# RevellerZero.net
KiCad netlist of a schematic drawn in EAGLE
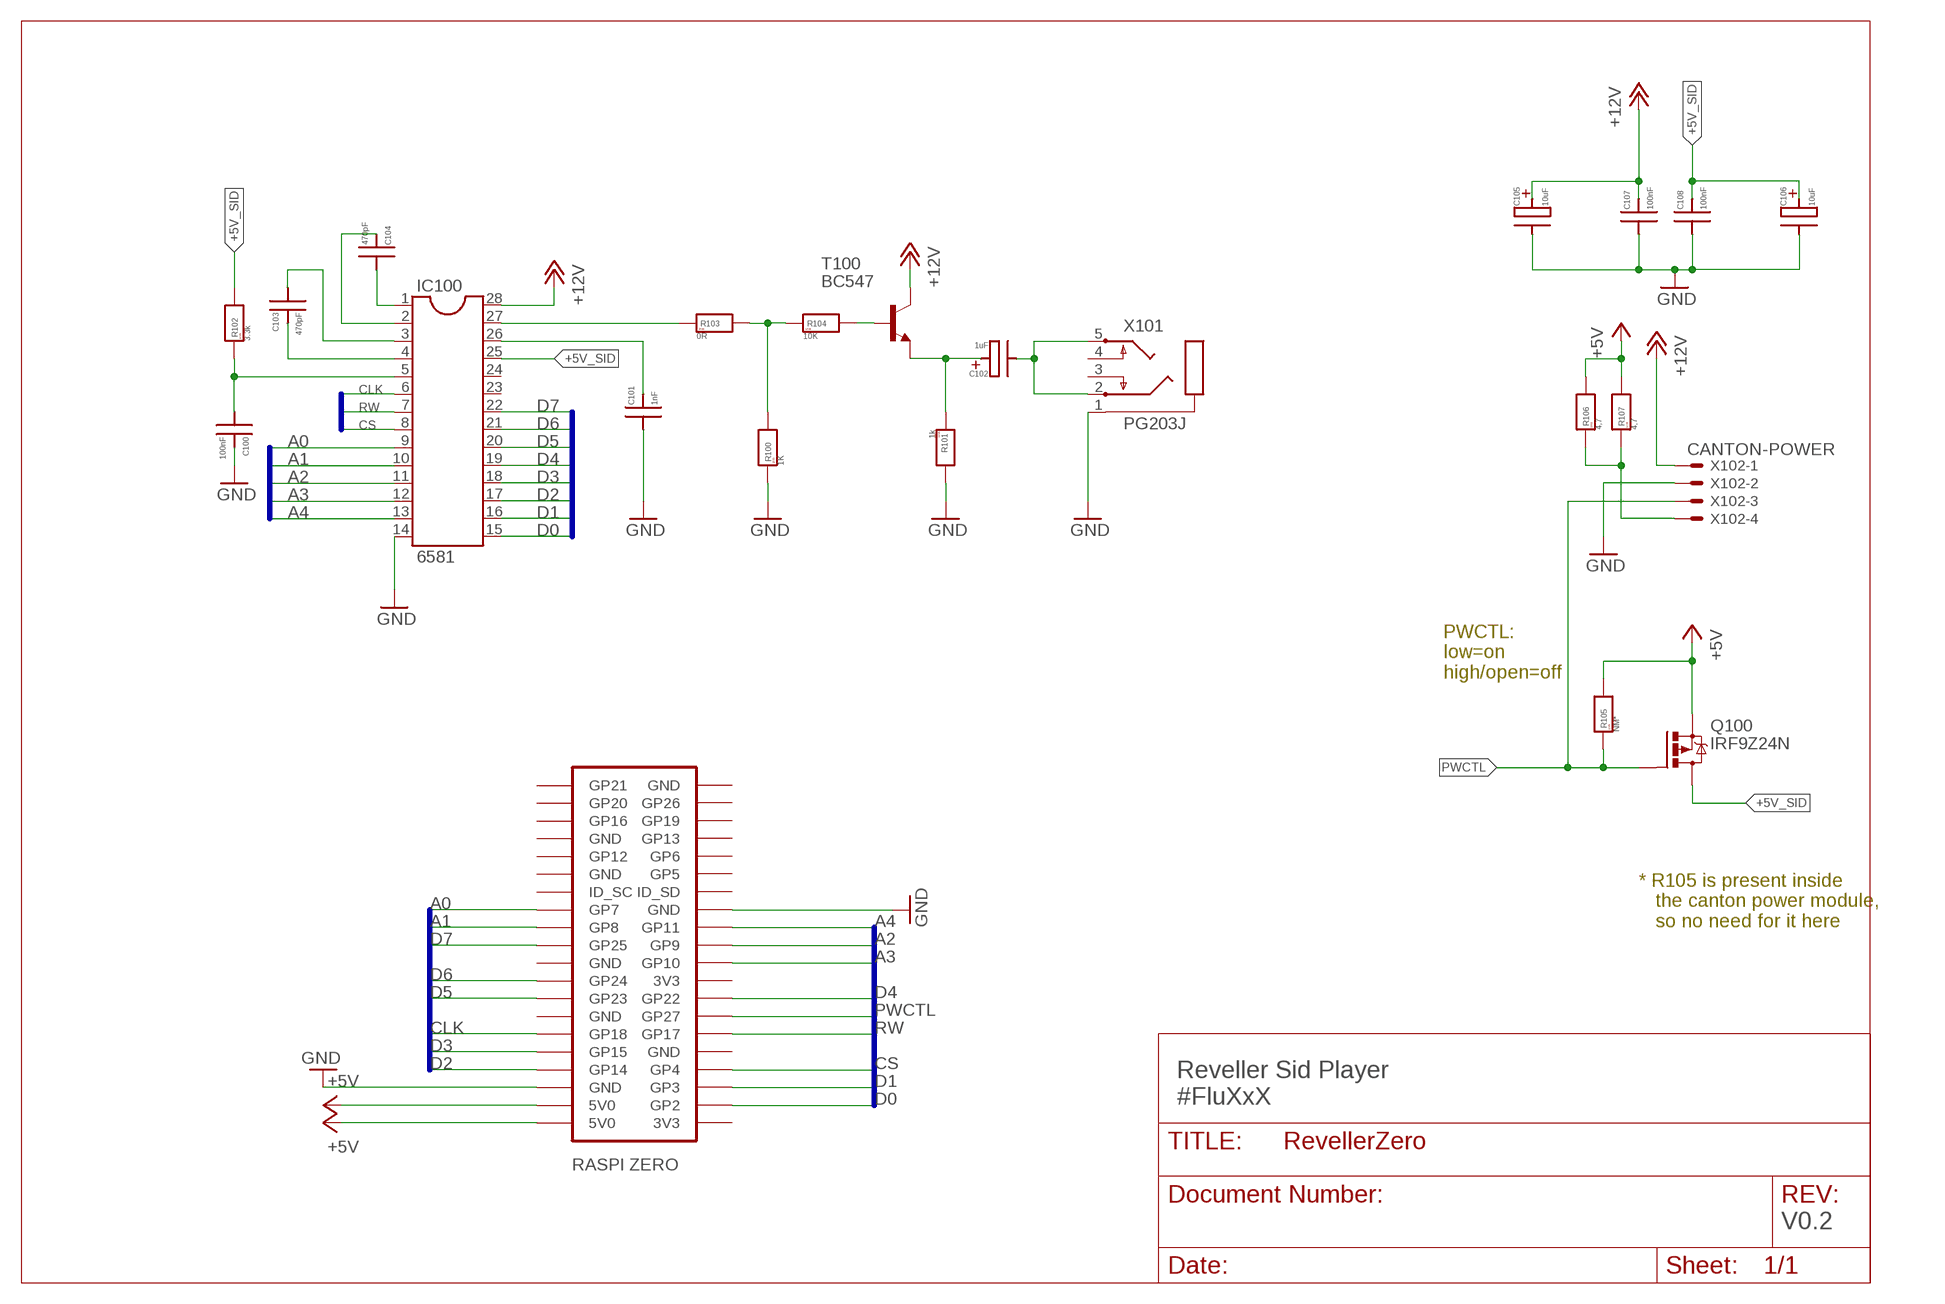
[diagram p0: schematic, sheet 1]

(export (version "E")
  (design (tool "Eeschema 10.0.6"))
  (components
    (comp (ref "C100")
      (value "100nF")
      (footprint "eagle-import:SMD-IPC_C1206")
      (libsource (lib "eagle-import") (part "SMD-IPC_CAPC1206"))
    )
    (comp (ref "C101")
      (value "1nF")
      (footprint "eagle-import:SMD-IPC_C1206")
      (libsource (lib "eagle-import") (part "SMD-IPC_CAPC1206"))
    )
    (comp (ref "C102")
      (value "1uF")
      (footprint "eagle-import:PXE-H")
      (libsource (lib "eagle-import") (part "SMD-IPC_CAPPOLPXE_H"))
    )
    (comp (ref "C103")
      (value "470pF")
      (footprint "eagle-import:SMD-IPC_C1206")
      (libsource (lib "eagle-import") (part "SMD-IPC_CAPC1206"))
    )
    (comp (ref "C104")
      (value "470pF")
      (footprint "eagle-import:SMD-IPC_C1206")
      (libsource (lib "eagle-import") (part "SMD-IPC_CAPC1206"))
    )
    (comp (ref "C105")
      (value "10uF")
      (footprint "eagle-import:SMD-IPC_CT7343")
      (libsource (lib "eagle-import") (part "SMD-IPC_CAPPOLC7343"))
    )
    (comp (ref "C106")
      (value "10uF")
      (footprint "eagle-import:SMD-IPC_CT7343")
      (libsource (lib "eagle-import") (part "SMD-IPC_CAPPOLC7343"))
    )
    (comp (ref "C107")
      (value "100nF")
      (footprint "eagle-import:SMD-IPC_C1206")
      (libsource (lib "eagle-import") (part "SMD-IPC_CAPC1206"))
    )
    (comp (ref "C108")
      (value "100nF")
      (footprint "eagle-import:SMD-IPC_C1206")
      (libsource (lib "eagle-import") (part "SMD-IPC_CAPC1206"))
    )
    (comp (ref "IC100")
      (value "6581")
      (footprint "eagle-import:DIL28-6")
      (libsource (lib "eagle-import") (part "DIL28"))
    )
    (comp (ref "Q100")
      (value "IRF9Z24N")
      (footprint "eagle-import:TO220BV")
      (libsource (lib "eagle-import") (part "IRF9530"))
    )
    (comp (ref "R100")
      (value "1K")
      (footprint "eagle-import:SMD-IPC_R1206")
      (libsource (lib "eagle-import") (part "SMD-IPC_RESR1206"))
    )
    (comp (ref "R101")
      (value "1k")
      (footprint "eagle-import:SMD-IPC_R1206")
      (libsource (lib "eagle-import") (part "SMD-IPC_RESR1206"))
    )
    (comp (ref "R102")
      (value "3.3k")
      (footprint "eagle-import:SMD-IPC_R1206")
      (libsource (lib "eagle-import") (part "SMD-IPC_RESR1206"))
    )
    (comp (ref "R103")
      (value "0R")
      (footprint "eagle-import:SMD-IPC_R1206")
      (libsource (lib "eagle-import") (part "SMD-IPC_RESR1206"))
    )
    (comp (ref "R104")
      (value "10K")
      (footprint "eagle-import:SMD-IPC_R1206")
      (libsource (lib "eagle-import") (part "SMD-IPC_RESR1206"))
    )
    (comp (ref "R105")
      (value "NM*")
      (footprint "eagle-import:SMD-IPC_R1206")
      (libsource (lib "eagle-import") (part "SMD-IPC_RESR1206"))
    )
    (comp (ref "R106")
      (value "4,7")
      (footprint "eagle-import:SMD-IPC_R1206")
      (libsource (lib "eagle-import") (part "SMD-IPC_RESR1206"))
    )
    (comp (ref "R107")
      (value "4,7")
      (footprint "eagle-import:SMD-IPC_R1206")
      (libsource (lib "eagle-import") (part "SMD-IPC_RESR1206"))
    )
    (comp (ref "T100")
      (value "BC547")
      (footprint "eagle-import:TO92")
      (libsource (lib "eagle-import") (part "BC547"))
    )
    (comp (ref "U$1")
      (value "ZERO")
      (footprint "eagle-import:ZERO")
      (libsource (lib "eagle-import") (part "ZERO"))
    )
    (comp (ref "X101")
      (value "PG203J")
      (footprint "eagle-import:PG203J")
      (libsource (lib "eagle-import") (part "PG203J"))
    )
    (comp (ref "X102")
      (value "CANTON-POWER")
      (footprint "eagle-import:22-23-2041")
      (fields (field (name "MF") "MOLEX") (field (name "MPN") "22-23-2041"))
      (libsource (lib "eagle-import") (part "22-23-2041"))
    )
  )
  (nets
    (net (code "1") (name "+5V") (class "Default")
      (node (ref "Q100") (pin "S") (pinfunction "S_S") (pintype "passive"))
      (node (ref "R105") (pin "2") (pinfunction "2_2") (pintype "passive"))
      (node (ref "R106") (pin "2") (pinfunction "2_2") (pintype "passive"))
      (node (ref "R107") (pin "2") (pinfunction "2_2") (pintype "passive"))
      (node (ref "U$1") (pin "2") (pinfunction "5V0_2") (pintype "bidirectional"))
      (node (ref "U$1") (pin "4") (pinfunction "5V0_4") (pintype "bidirectional"))
    )
    (net (code "2") (name "+5V_SID") (class "Default")
      (node (ref "C106") (pin "+") (pinfunction "+_+") (pintype "passive"))
      (node (ref "C108") (pin "+") (pinfunction "2_+") (pintype "passive"))
      (node (ref "IC100") (pin "25") (pinfunction "25_25") (pintype "passive"))
      (node (ref "Q100") (pin "D") (pinfunction "D_D") (pintype "passive"))
      (node (ref "R102") (pin "2") (pinfunction "2_2") (pintype "passive"))
    )
    (net (code "3") (name "+12V") (class "Default")
      (node (ref "C105") (pin "+") (pinfunction "+_+") (pintype "passive"))
      (node (ref "C107") (pin "+") (pinfunction "2_+") (pintype "passive"))
      (node (ref "IC100") (pin "28") (pinfunction "28_28") (pintype "passive"))
      (node (ref "T100") (pin "3") (pinfunction "C_3") (pintype "passive"))
      (node (ref "X102") (pin "1") (pinfunction "S_1") (pintype "passive"))
    )
    (net (code "4") (name "/A0") (class "Default")
      (node (ref "IC100") (pin "9") (pinfunction "9_9") (pintype "passive"))
      (node (ref "U$1") (pin "26") (pinfunction "GP7_26") (pintype "bidirectional"))
    )
    (net (code "5") (name "/A1") (class "Default")
      (node (ref "IC100") (pin "10") (pinfunction "10_10") (pintype "passive"))
      (node (ref "U$1") (pin "24") (pinfunction "GP8_24") (pintype "bidirectional"))
    )
    (net (code "6") (name "/A2") (class "Default")
      (node (ref "IC100") (pin "11") (pinfunction "11_11") (pintype "passive"))
      (node (ref "U$1") (pin "21") (pinfunction "GP9_21") (pintype "bidirectional"))
    )
    (net (code "7") (name "/A3") (class "Default")
      (node (ref "IC100") (pin "12") (pinfunction "12_12") (pintype "passive"))
      (node (ref "U$1") (pin "19") (pinfunction "GP10_19") (pintype "bidirectional"))
    )
    (net (code "8") (name "/A4") (class "Default")
      (node (ref "IC100") (pin "13") (pinfunction "13_13") (pintype "passive"))
      (node (ref "U$1") (pin "23") (pinfunction "GP11_23") (pintype "bidirectional"))
    )
    (net (code "9") (name "/CLK") (class "Default")
      (node (ref "IC100") (pin "6") (pinfunction "6_6") (pintype "passive"))
      (node (ref "U$1") (pin "12") (pinfunction "GP18_12") (pintype "bidirectional"))
    )
    (net (code "10") (name "/CS") (class "Default")
      (node (ref "IC100") (pin "8") (pinfunction "8_8") (pintype "passive"))
      (node (ref "U$1") (pin "7") (pinfunction "GP4_7") (pintype "bidirectional"))
    )
    (net (code "11") (name "/D0") (class "Default")
      (node (ref "IC100") (pin "15") (pinfunction "15_15") (pintype "passive"))
      (node (ref "U$1") (pin "3") (pinfunction "GP2_3") (pintype "bidirectional"))
    )
    (net (code "12") (name "/D1") (class "Default")
      (node (ref "IC100") (pin "16") (pinfunction "16_16") (pintype "passive"))
      (node (ref "U$1") (pin "5") (pinfunction "GP3_5") (pintype "bidirectional"))
    )
    (net (code "13") (name "/D2") (class "Default")
      (node (ref "IC100") (pin "17") (pinfunction "17_17") (pintype "passive"))
      (node (ref "U$1") (pin "8") (pinfunction "GP14_8") (pintype "bidirectional"))
    )
    (net (code "14") (name "/D3") (class "Default")
      (node (ref "IC100") (pin "18") (pinfunction "18_18") (pintype "passive"))
      (node (ref "U$1") (pin "10") (pinfunction "GP15_10") (pintype "bidirectional"))
    )
    (net (code "15") (name "/D4") (class "Default")
      (node (ref "IC100") (pin "19") (pinfunction "19_19") (pintype "passive"))
      (node (ref "U$1") (pin "15") (pinfunction "GP22_15") (pintype "bidirectional"))
    )
    (net (code "16") (name "/D5") (class "Default")
      (node (ref "IC100") (pin "20") (pinfunction "20_20") (pintype "passive"))
      (node (ref "U$1") (pin "16") (pinfunction "GP23_16") (pintype "bidirectional"))
    )
    (net (code "17") (name "/D6") (class "Default")
      (node (ref "IC100") (pin "21") (pinfunction "21_21") (pintype "passive"))
      (node (ref "U$1") (pin "18") (pinfunction "GP24_18") (pintype "bidirectional"))
    )
    (net (code "18") (name "/D7") (class "Default")
      (node (ref "IC100") (pin "22") (pinfunction "22_22") (pintype "passive"))
      (node (ref "U$1") (pin "22") (pinfunction "GP25_22") (pintype "bidirectional"))
    )
    (net (code "19") (name "/RW") (class "Default")
      (node (ref "IC100") (pin "7") (pinfunction "7_7") (pintype "passive"))
      (node (ref "U$1") (pin "11") (pinfunction "GP17_11") (pintype "bidirectional"))
    )
    (net (code "20") (name "GND") (class "Default")
      (node (ref "C100") (pin "+") (pinfunction "2_+") (pintype "passive"))
      (node (ref "C101") (pin "-") (pinfunction "1_-") (pintype "passive"))
      (node (ref "C105") (pin "-") (pinfunction "-_-") (pintype "passive"))
      (node (ref "C106") (pin "-") (pinfunction "-_-") (pintype "passive"))
      (node (ref "C107") (pin "-") (pinfunction "1_-") (pintype "passive"))
      (node (ref "C108") (pin "-") (pinfunction "1_-") (pintype "passive"))
      (node (ref "IC100") (pin "14") (pinfunction "14_14") (pintype "passive"))
      (node (ref "R100") (pin "1") (pinfunction "1_1") (pintype "passive"))
      (node (ref "R101") (pin "2") (pinfunction "2_2") (pintype "passive"))
      (node (ref "U$1") (pin "25") (pinfunction "GND_25") (pintype "bidirectional"))
      (node (ref "U$1") (pin "6") (pinfunction "GND_6") (pintype "bidirectional"))
      (node (ref "X101") (pin "1") (pinfunction "1_1") (pintype "passive"))
      (node (ref "X102") (pin "2") (pinfunction "S_2") (pintype "passive"))
    )
    (net (code "21") (name "Net-(C100-1)") (class "Default")
      (node (ref "C100") (pin "-") (pinfunction "1_-") (pintype "passive"))
      (node (ref "IC100") (pin "5") (pinfunction "5_5") (pintype "passive"))
      (node (ref "R102") (pin "1") (pinfunction "1_1") (pintype "passive"))
    )
    (net (code "22") (name "Net-(C101-2)") (class "Default")
      (node (ref "C101") (pin "+") (pinfunction "2_+") (pintype "passive"))
      (node (ref "IC100") (pin "26") (pinfunction "26_26") (pintype "passive"))
    )
    (net (code "23") (name "Net-(C102-Pad-)") (class "Default")
      (node (ref "C102") (pin "-") (pinfunction "-_-") (pintype "passive"))
      (node (ref "X101") (pin "2") (pinfunction "2_2") (pintype "passive"))
      (node (ref "X101") (pin "5") (pinfunction "5_5") (pintype "passive"))
    )
    (net (code "24") (name "Net-(C103-1)") (class "Default")
      (node (ref "C103") (pin "-") (pinfunction "1_-") (pintype "passive"))
      (node (ref "IC100") (pin "3") (pinfunction "3_3") (pintype "passive"))
    )
    (net (code "25") (name "Net-(C103-2)") (class "Default")
      (node (ref "C103") (pin "+") (pinfunction "2_+") (pintype "passive"))
      (node (ref "IC100") (pin "4") (pinfunction "4_4") (pintype "passive"))
    )
    (net (code "26") (name "Net-(C104-1)") (class "Default")
      (node (ref "C104") (pin "-") (pinfunction "1_-") (pintype "passive"))
      (node (ref "IC100") (pin "1") (pinfunction "1_1") (pintype "passive"))
    )
    (net (code "27") (name "Net-(C104-2)") (class "Default")
      (node (ref "C104") (pin "+") (pinfunction "2_+") (pintype "passive"))
      (node (ref "IC100") (pin "2") (pinfunction "2_2") (pintype "passive"))
    )
    (net (code "28") (name "Net-(IC100-Pad27)") (class "Default")
      (node (ref "IC100") (pin "27") (pinfunction "27_27") (pintype "passive"))
      (node (ref "R103") (pin "1") (pinfunction "1_1") (pintype "passive"))
    )
    (net (code "29") (name "Net-(R100-Pad2)") (class "Default")
      (node (ref "R100") (pin "2") (pinfunction "2_2") (pintype "passive"))
      (node (ref "R103") (pin "2") (pinfunction "2_2") (pintype "passive"))
      (node (ref "R104") (pin "1") (pinfunction "1_1") (pintype "passive"))
    )
    (net (code "30") (name "Net-(T100-B)") (class "Default")
      (node (ref "R104") (pin "2") (pinfunction "2_2") (pintype "passive"))
      (node (ref "T100") (pin "2") (pinfunction "B_2") (pintype "passive"))
    )
    (net (code "31") (name "Net-(T100-E)") (class "Default")
      (node (ref "C102") (pin "+") (pinfunction "+_+") (pintype "passive"))
      (node (ref "R101") (pin "1") (pinfunction "1_1") (pintype "passive"))
      (node (ref "T100") (pin "1") (pinfunction "E_1") (pintype "passive"))
    )
    (net (code "32") (name "Net-(X102D-S)") (class "Default")
      (node (ref "R106") (pin "1") (pinfunction "1_1") (pintype "passive"))
      (node (ref "R107") (pin "1") (pinfunction "1_1") (pintype "passive"))
      (node (ref "X102") (pin "4") (pinfunction "S_4") (pintype "passive"))
    )
    (net (code "33") (name "PWCTL") (class "Default")
      (node (ref "Q100") (pin "G") (pinfunction "G_G") (pintype "passive"))
      (node (ref "R105") (pin "1") (pinfunction "1_1") (pintype "passive"))
      (node (ref "U$1") (pin "13") (pinfunction "GP27_13") (pintype "bidirectional"))
      (node (ref "X102") (pin "3") (pinfunction "S_3") (pintype "passive"))
    )
    (net (code "34") (name "unconnected-(IC100-Pad23)") (class "Default")
      (node (ref "IC100") (pin "23") (pinfunction "23_23") (pintype "passive"))
    )
    (net (code "35") (name "unconnected-(IC100-Pad24)") (class "Default")
      (node (ref "IC100") (pin "24") (pinfunction "24_24") (pintype "passive"))
    )
    (net (code "36") (name "unconnected-(U$1-3V3-Pad1)") (class "Default")
      (node (ref "U$1") (pin "1") (pinfunction "3V3_1") (pintype "bidirectional"))
    )
    (net (code "37") (name "unconnected-(U$1-3V3-Pad17)") (class "Default")
      (node (ref "U$1") (pin "17") (pinfunction "3V3_17") (pintype "bidirectional"))
    )
    (net (code "38") (name "unconnected-(U$1-GND-Pad9)") (class "Default")
      (node (ref "U$1") (pin "9") (pinfunction "GND_9") (pintype "bidirectional"))
    )
    (net (code "39") (name "unconnected-(U$1-GND-Pad14)") (class "Default")
      (node (ref "U$1") (pin "14") (pinfunction "GND_14") (pintype "bidirectional"))
    )
    (net (code "40") (name "unconnected-(U$1-GND-Pad20)") (class "Default")
      (node (ref "U$1") (pin "20") (pinfunction "GND_20") (pintype "bidirectional"))
    )
    (net (code "41") (name "unconnected-(U$1-GND-Pad30)") (class "Default")
      (node (ref "U$1") (pin "30") (pinfunction "GND_30") (pintype "bidirectional"))
    )
    (net (code "42") (name "unconnected-(U$1-GND-Pad34)") (class "Default")
      (node (ref "U$1") (pin "34") (pinfunction "GND_34") (pintype "bidirectional"))
    )
    (net (code "43") (name "unconnected-(U$1-GND-Pad39)") (class "Default")
      (node (ref "U$1") (pin "39") (pinfunction "GND_39") (pintype "bidirectional"))
    )
    (net (code "44") (name "unconnected-(U$1-GP5-Pad29)") (class "Default")
      (node (ref "U$1") (pin "29") (pinfunction "GP5_29") (pintype "bidirectional"))
    )
    (net (code "45") (name "unconnected-(U$1-GP6-Pad31)") (class "Default")
      (node (ref "U$1") (pin "31") (pinfunction "GP6_31") (pintype "bidirectional"))
    )
    (net (code "46") (name "unconnected-(U$1-GP12-Pad32)") (class "Default")
      (node (ref "U$1") (pin "32") (pinfunction "GP12_32") (pintype "bidirectional"))
    )
    (net (code "47") (name "unconnected-(U$1-GP13-Pad33)") (class "Default")
      (node (ref "U$1") (pin "33") (pinfunction "GP13_33") (pintype "bidirectional"))
    )
    (net (code "48") (name "unconnected-(U$1-GP16-Pad36)") (class "Default")
      (node (ref "U$1") (pin "36") (pinfunction "GP16_36") (pintype "bidirectional"))
    )
    (net (code "49") (name "unconnected-(U$1-GP19-Pad35)") (class "Default")
      (node (ref "U$1") (pin "35") (pinfunction "GP19_35") (pintype "bidirectional"))
    )
    (net (code "50") (name "unconnected-(U$1-GP20-Pad38)") (class "Default")
      (node (ref "U$1") (pin "38") (pinfunction "GP20_38") (pintype "bidirectional"))
    )
    (net (code "51") (name "unconnected-(U$1-GP21-Pad40)") (class "Default")
      (node (ref "U$1") (pin "40") (pinfunction "GP21_40") (pintype "bidirectional"))
    )
    (net (code "52") (name "unconnected-(U$1-GP26-Pad37)") (class "Default")
      (node (ref "U$1") (pin "37") (pinfunction "GP26_37") (pintype "bidirectional"))
    )
    (net (code "53") (name "unconnected-(U$1-ID_SC-Pad28)") (class "Default")
      (node (ref "U$1") (pin "28") (pinfunction "ID_SC_28") (pintype "bidirectional"))
    )
    (net (code "54") (name "unconnected-(U$1-ID_SD-Pad27)") (class "Default")
      (node (ref "U$1") (pin "27") (pinfunction "ID_SD_27") (pintype "bidirectional"))
    )
    (net (code "55") (name "unconnected-(X101-Pad3)") (class "Default")
      (node (ref "X101") (pin "3") (pinfunction "3_3") (pintype "passive"))
    )
    (net (code "56") (name "unconnected-(X101-Pad4)") (class "Default")
      (node (ref "X101") (pin "4") (pinfunction "4_4") (pintype "passive"))
    )
  )
)
